# Sheet3.net
KiCad netlist of a schematic drawn in Altium Designer
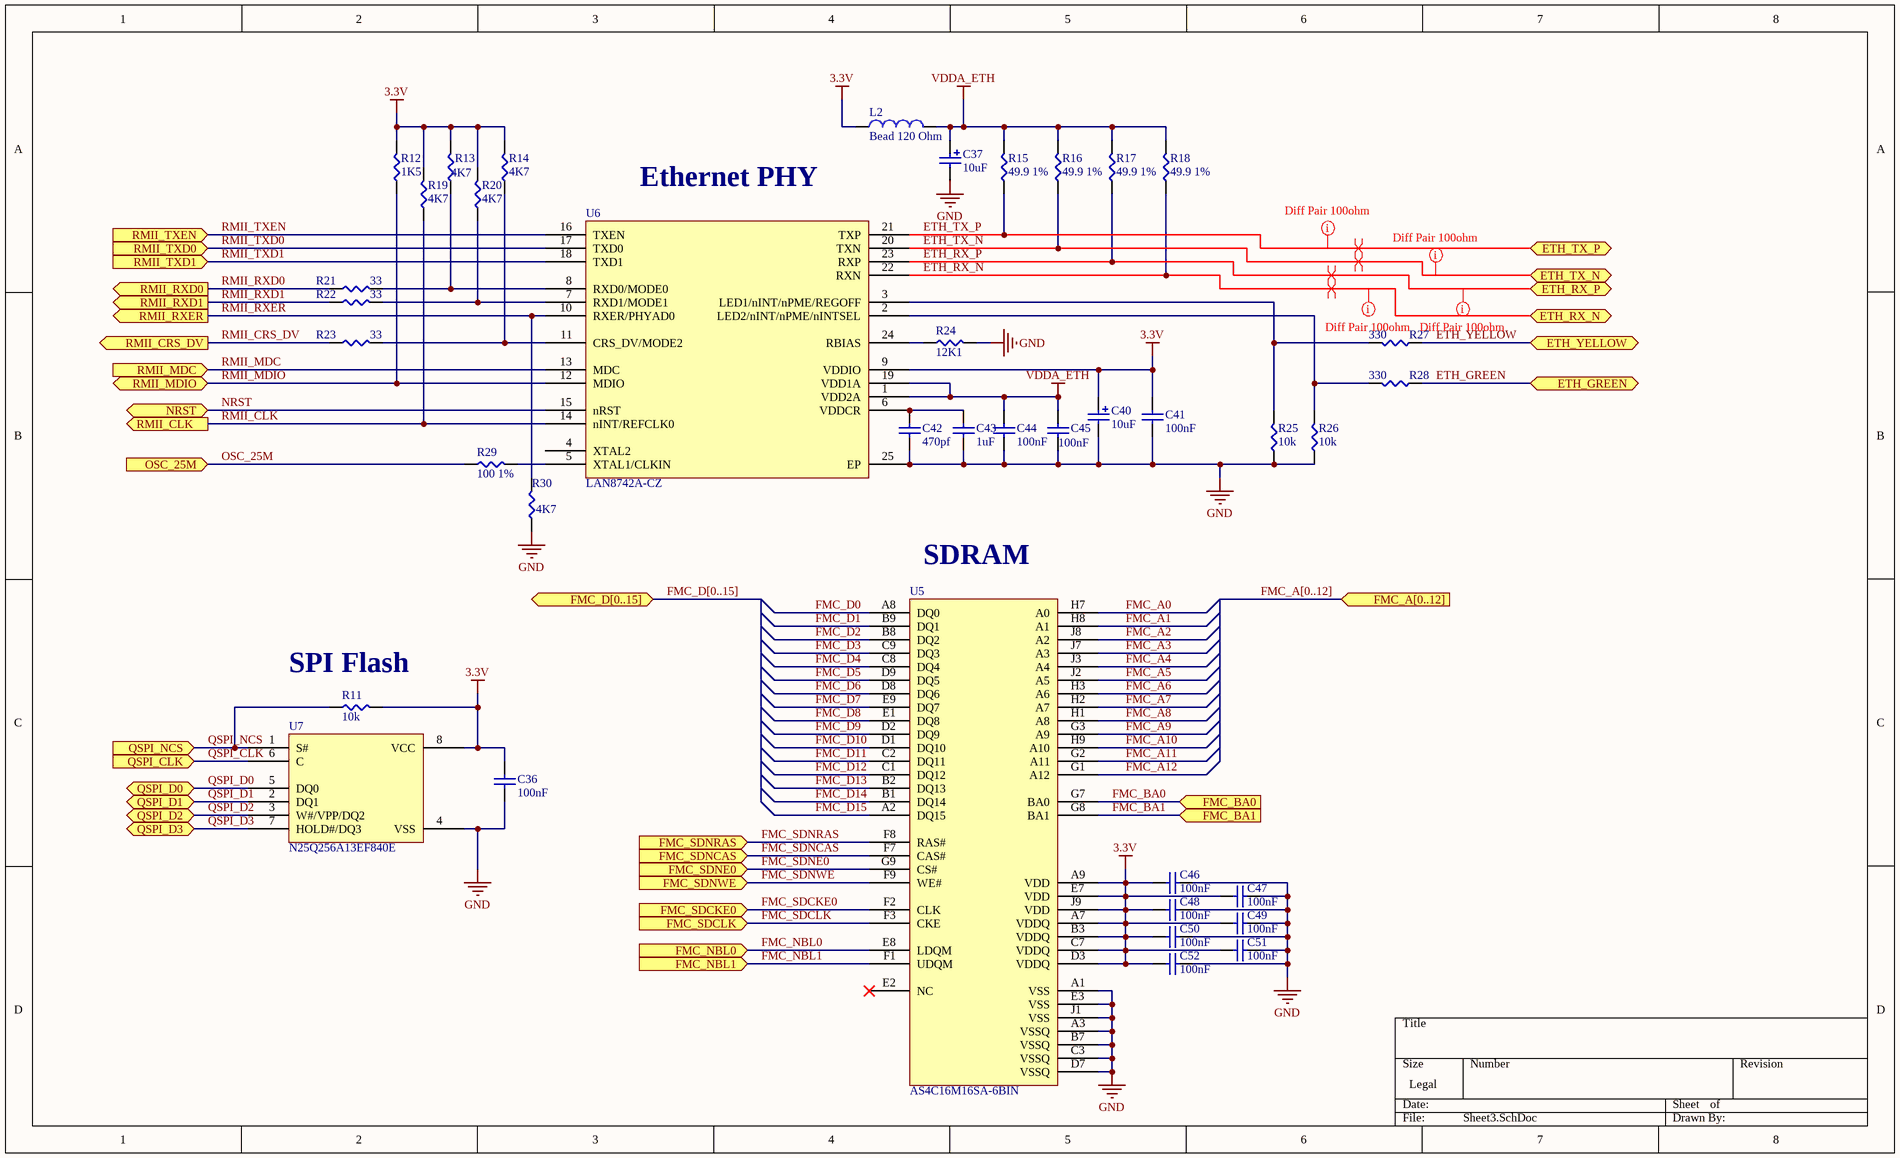
[diagram p0: Sheet3.SchDoc]

(export (version "E")
  (design (tool "Eeschema 10.0.6"))
  (components
    (comp (ref "C36")
      (value "100nF")
      (footprint "CAP0402X04M")
      (description "CAP CER 0.1UF 16V X7R 0402")
      (fields
        (field (name "MANUFACTURER") "Murata Electronics North America")
        (field (name "MANUFACTURER PART NUMBER") "GRM155R71C104KA88J")
      )
      (libsource (lib "Main") (part "GRM155R71C104KA88J"))
    )
    (comp (ref "C37")
      (value "10uF")
      (footprint "CAPPOL1206X07M")
      (description "CAP TANT 10UF 10V 10% 1206")
      (fields
        (field (name "MANUFACTURER") "Vishay Sprague")
        (field (name "MANUFACTURER PART NUMBER") "293D106X9010A2TE3")
      )
      (libsource (lib "Main") (part "293D106X9010A2TE3"))
    )
    (comp (ref "C40")
      (value "10uF")
      (footprint "CAPPOL1206X07M")
      (description "CAP TANT 10UF 10V 10% 1206")
      (fields
        (field (name "MANUFACTURER") "Vishay Sprague")
        (field (name "MANUFACTURER PART NUMBER") "293D106X9010A2TE3")
      )
      (libsource (lib "Main") (part "293D106X9010A2TE3"))
    )
    (comp (ref "C41")
      (value "100nF")
      (footprint "CAP0402X04M")
      (description "CAP CER 0.1UF 16V X7R 0402")
      (fields
        (field (name "MANUFACTURER") "Murata Electronics North America")
        (field (name "MANUFACTURER PART NUMBER") "GRM155R71C104KA88J")
      )
      (libsource (lib "Main") (part "GRM155R71C104KA88J"))
    )
    (comp (ref "C42")
      (value "470pf")
      (footprint "CAP0402X04M")
      (description "CAP CER 470PF 50V X7R 0402")
      (fields
        (field (name "MANUFACTURER") "Samsung Electro-Mechanics America, Inc.")
        (field (name "MANUFACTURER PART NUMBER") "CL05B471KB5NNNC")
      )
      (libsource (lib "Main") (part "CL05B471KB5NNNC"))
    )
    (comp (ref "C43")
      (value "1uF")
      (footprint "CAP0402X04M")
      (description "CAP CER 1UF 6.3V X5R 0402")
      (fields
        (field (name "MANUFACTURER") "Murata Electronics North America")
        (field (name "MANUFACTURER PART NUMBER") "GRM155R60J105KE19D")
      )
      (libsource (lib "Main") (part "GRM155R60J105KE19D"))
    )
    (comp (ref "C44")
      (value "100nF")
      (footprint "CAP0402X04M")
      (description "CAP CER 0.1UF 16V X7R 0402")
      (fields
        (field (name "MANUFACTURER") "Murata Electronics North America")
        (field (name "MANUFACTURER PART NUMBER") "GRM155R71C104KA88J")
      )
      (libsource (lib "Main") (part "GRM155R71C104KA88J"))
    )
    (comp (ref "C45")
      (value "100nF")
      (footprint "CAP0402X04M")
      (description "CAP CER 0.1UF 16V X7R 0402")
      (fields
        (field (name "MANUFACTURER") "Murata Electronics North America")
        (field (name "MANUFACTURER PART NUMBER") "GRM155R71C104KA88J")
      )
      (libsource (lib "Main") (part "GRM155R71C104KA88J"))
    )
    (comp (ref "C46")
      (value "100nF")
      (footprint "CAP0402X04M")
      (description "CAP CER 0.1UF 16V X7R 0402")
      (fields
        (field (name "MANUFACTURER") "Murata Electronics North America")
        (field (name "MANUFACTURER PART NUMBER") "GRM155R71C104KA88J")
      )
      (libsource (lib "Main") (part "GRM155R71C104KA88J"))
    )
    (comp (ref "C47")
      (value "100nF")
      (footprint "CAP0402X04M")
      (description "CAP CER 0.1UF 16V X7R 0402")
      (fields
        (field (name "MANUFACTURER") "Murata Electronics North America")
        (field (name "MANUFACTURER PART NUMBER") "GRM155R71C104KA88J")
      )
      (libsource (lib "Main") (part "GRM155R71C104KA88J"))
    )
    (comp (ref "C48")
      (value "100nF")
      (footprint "CAP0402X04ROUND")
      (description "CAP CER 0.1UF 16V X7R 0402")
      (fields
        (field (name "MANUFACTURER") "Murata Electronics North America")
        (field (name "MANUFACTURER PART NUMBER") "GRM155R71C104KA88J")
      )
      (libsource (lib "Main") (part "GRM155R71C104KA88J"))
    )
    (comp (ref "C49")
      (value "100nF")
      (footprint "CAP0402X04ROUND")
      (description "CAP CER 0.1UF 16V X7R 0402")
      (fields
        (field (name "MANUFACTURER") "Murata Electronics North America")
        (field (name "MANUFACTURER PART NUMBER") "GRM155R71C104KA88J")
      )
      (libsource (lib "Main") (part "GRM155R71C104KA88J"))
    )
    (comp (ref "C50")
      (value "100nF")
      (footprint "CAP0402X04ROUND")
      (description "CAP CER 0.1UF 16V X7R 0402")
      (fields
        (field (name "MANUFACTURER") "Murata Electronics North America")
        (field (name "MANUFACTURER PART NUMBER") "GRM155R71C104KA88J")
      )
      (libsource (lib "Main") (part "GRM155R71C104KA88J"))
    )
    (comp (ref "C51")
      (value "100nF")
      (footprint "CAP0402X04ROUND")
      (description "CAP CER 0.1UF 16V X7R 0402")
      (fields
        (field (name "MANUFACTURER") "Murata Electronics North America")
        (field (name "MANUFACTURER PART NUMBER") "GRM155R71C104KA88J")
      )
      (libsource (lib "Main") (part "GRM155R71C104KA88J"))
    )
    (comp (ref "C52")
      (value "100nF")
      (footprint "CAP0402X04ROUND")
      (description "CAP CER 0.1UF 16V X7R 0402")
      (fields
        (field (name "MANUFACTURER") "Murata Electronics North America")
        (field (name "MANUFACTURER PART NUMBER") "GRM155R71C104KA88J")
      )
      (libsource (lib "Main") (part "GRM155R71C104KA88J"))
    )
    (comp (ref "L2")
      (value "Bead 120 Ohm")
      (footprint "IND0603X055M")
      (description "FERRITE BEAD 120 OHM 0603 1LN")
      (fields
        (field (name "MANUFACTURER") "Murata Electronics North America")
        (field (name "MANUFACTURER PART NUMBER") "BLM18PG121SN1D")
      )
      (libsource (lib "Main") (part "BLM18PG121SN1D"))
    )
    (comp (ref "R11")
      (value "10k")
      (footprint "RES0402X04M")
      (description "RES SMD 10K OHM 1% 1/16W 0402")
      (fields
        (field (name "MANUFACTURER") "Yageo")
        (field (name "MANUFACTURER PART NUMBER") "RC0402FR-0710KL")
      )
      (libsource (lib "Main") (part "RC0402FR-0710KL"))
    )
    (comp (ref "R12")
      (value "1K5")
      (footprint "RES0402X04M")
      (description "RES SMD 1.5K OHM 1% 1/10W 0402")
      (fields
        (field (name "MANUFACTURER") "Panasonic Electronic Components")
        (field (name "MANUFACTURER PART NUMBER") "ERJ-2RKF1501X")
      )
      (libsource (lib "Main") (part "ERJ-2RKF1501X"))
    )
    (comp (ref "R13")
      (value "4K7")
      (footprint "RES0402X04M")
      (description "RES SMD 4.7K OHM 1% 1/10W 0402")
      (fields
        (field (name "MANUFACTURER") "Panasonic Electronic Components")
        (field (name "MANUFACTURER PART NUMBER") "ERJ-2RKF4701X")
      )
      (libsource (lib "Main") (part "ERJ-2RKF4701X"))
    )
    (comp (ref "R14")
      (value "4K7")
      (footprint "RES0402X04M")
      (description "RES SMD 4.7K OHM 1% 1/10W 0402")
      (fields
        (field (name "MANUFACTURER") "Panasonic Electronic Components")
        (field (name "MANUFACTURER PART NUMBER") "ERJ-2RKF4701X")
      )
      (libsource (lib "Main") (part "ERJ-2RKF4701X"))
    )
    (comp (ref "R15")
      (value "49.9 1%")
      (footprint "RES0402X04M")
      (description "RES SMD 49.9 OHM 1% 1/16W 0402")
      (fields
        (field (name "MANUFACTURER") "Yageo")
        (field (name "MANUFACTURER PART NUMBER") "RC0402FR-0749R9L")
      )
      (libsource (lib "Main") (part "RC0402FR-0749R9L"))
    )
    (comp (ref "R16")
      (value "49.9 1%")
      (footprint "RES0402X04M")
      (description "RES SMD 49.9 OHM 1% 1/16W 0402")
      (fields
        (field (name "MANUFACTURER") "Yageo")
        (field (name "MANUFACTURER PART NUMBER") "RC0402FR-0749R9L")
      )
      (libsource (lib "Main") (part "RC0402FR-0749R9L"))
    )
    (comp (ref "R17")
      (value "49.9 1%")
      (footprint "RES0402X04M")
      (description "RES SMD 49.9 OHM 1% 1/16W 0402")
      (fields
        (field (name "MANUFACTURER") "Yageo")
        (field (name "MANUFACTURER PART NUMBER") "RC0402FR-0749R9L")
      )
      (libsource (lib "Main") (part "RC0402FR-0749R9L"))
    )
    (comp (ref "R18")
      (value "49.9 1%")
      (footprint "RES0402X04M")
      (description "RES SMD 49.9 OHM 1% 1/16W 0402")
      (fields
        (field (name "MANUFACTURER") "Yageo")
        (field (name "MANUFACTURER PART NUMBER") "RC0402FR-0749R9L")
      )
      (libsource (lib "Main") (part "RC0402FR-0749R9L"))
    )
    (comp (ref "R19")
      (value "4K7")
      (footprint "RES0402X04M")
      (description "RES SMD 4.7K OHM 1% 1/10W 0402")
      (fields
        (field (name "MANUFACTURER") "Panasonic Electronic Components")
        (field (name "MANUFACTURER PART NUMBER") "ERJ-2RKF4701X")
      )
      (libsource (lib "Main") (part "ERJ-2RKF4701X"))
    )
    (comp (ref "R20")
      (value "4K7")
      (footprint "RES0402X04M")
      (description "RES SMD 4.7K OHM 1% 1/10W 0402")
      (fields
        (field (name "MANUFACTURER") "Panasonic Electronic Components")
        (field (name "MANUFACTURER PART NUMBER") "ERJ-2RKF4701X")
      )
      (libsource (lib "Main") (part "ERJ-2RKF4701X"))
    )
    (comp (ref "R21")
      (value "33")
      (footprint "RES0402X04M")
      (description "RES SMD 33 OHM 1% 1/10W 0402")
      (fields
        (field (name "MANUFACTURER") "Panasonic Electronic Components")
        (field (name "MANUFACTURER PART NUMBER") "ERJ-2RKF33R0X")
      )
      (libsource (lib "Main") (part "ERJ-2RKF33R0X"))
    )
    (comp (ref "R22")
      (value "33")
      (footprint "RES0402X04M")
      (description "RES SMD 33 OHM 1% 1/10W 0402")
      (fields
        (field (name "MANUFACTURER") "Panasonic Electronic Components")
        (field (name "MANUFACTURER PART NUMBER") "ERJ-2RKF33R0X")
      )
      (libsource (lib "Main") (part "ERJ-2RKF33R0X"))
    )
    (comp (ref "R23")
      (value "33")
      (footprint "RES0402X04M")
      (description "RES SMD 33 OHM 1% 1/10W 0402")
      (fields
        (field (name "MANUFACTURER") "Panasonic Electronic Components")
        (field (name "MANUFACTURER PART NUMBER") "ERJ-2RKF33R0X")
      )
      (libsource (lib "Main") (part "ERJ-2RKF33R0X"))
    )
    (comp (ref "R24")
      (value "12K1")
      (footprint "RES0402X04M")
      (description "RES SMD 12.1K OHM 1% 1/10W 0402")
      (fields
        (field (name "MANUFACTURER") "Panasonic Electronic Components")
        (field (name "MANUFACTURER PART NUMBER") "ERJ-2RKF1212X")
      )
      (libsource (lib "Main") (part "ERJ-2RKF1212X"))
    )
    (comp (ref "R25")
      (value "10k")
      (footprint "RES0402X04M")
      (description "RES SMD 10K OHM 1% 1/16W 0402")
      (fields
        (field (name "MANUFACTURER") "Yageo")
        (field (name "MANUFACTURER PART NUMBER") "RC0402FR-0710KL")
      )
      (libsource (lib "Main") (part "RC0402FR-0710KL"))
    )
    (comp (ref "R26")
      (value "10k")
      (footprint "RES0402X04M")
      (description "RES SMD 10K OHM 1% 1/16W 0402")
      (fields
        (field (name "MANUFACTURER") "Yageo")
        (field (name "MANUFACTURER PART NUMBER") "RC0402FR-0710KL")
      )
      (libsource (lib "Main") (part "RC0402FR-0710KL"))
    )
    (comp (ref "R27")
      (value "330")
      (footprint "RES0402X04M")
      (description "RES SMD 330 OHM 1% 1/10W 0402")
      (fields
        (field (name "MANUFACTURER") "Panasonic Electronic Components")
        (field (name "MANUFACTURER PART NUMBER") "ERJ-2RKF3300X")
      )
      (libsource (lib "Main") (part "ERJ-2RKF3300X"))
    )
    (comp (ref "R28")
      (value "330")
      (footprint "RES0402X04M")
      (description "RES SMD 330 OHM 1% 1/10W 0402")
      (fields
        (field (name "MANUFACTURER") "Panasonic Electronic Components")
        (field (name "MANUFACTURER PART NUMBER") "ERJ-2RKF3300X")
      )
      (libsource (lib "Main") (part "ERJ-2RKF3300X"))
    )
    (comp (ref "R29")
      (value "100 1%")
      (footprint "RES0402X04M")
      (description "RES SMD 100 OHM 1% 1/16W 0402")
      (fields
        (field (name "MANUFACTURER") "Yageo")
        (field (name "MANUFACTURER PART NUMBER") "RC0402FR-07100RL")
      )
      (libsource (lib "Main") (part "RC0402FR-07100RL"))
    )
    (comp (ref "R30")
      (value "4K7")
      (footprint "RES0402X04M")
      (description "RES SMD 4.7K OHM 1% 1/10W 0402")
      (fields
        (field (name "MANUFACTURER") "Panasonic Electronic Components")
        (field (name "MANUFACTURER PART NUMBER") "ERJ-2RKF4701X")
      )
      (libsource (lib "Main") (part "ERJ-2RKF4701X"))
    )
    (comp (ref "U5")
      (value "AS4C16M16SA-6BIN")
      (footprint "BGA100P9X9-54A")
      (description "IC SDRAM 256MBIT 166MHZ 54BGA")
      (fields (field (name "MANUFACTURER") "Alliance Memory, Inc."))
      (libsource (lib "Main") (part "AS4C16M16SA-6BIN"))
    )
    (comp (ref "U6")
      (value "LAN8742A-CZ")
      (footprint "QFN50P400X400X100_HS-25N")
      (description "IC TXRX ETHERNET 100MBPS 24QFN")
      (fields (field (name "MANUFACTURER") "Microchip Technology"))
      (libsource (lib "Main") (part "LAN8742A-CZ"))
    )
    (comp (ref "U7")
      (value "N25Q256A13EF840E")
      (footprint "SON127P800X100_HS-9N")
      (description "IC FLASH 256MBIT 108MHZ 8VPDFN")
      (fields (field (name "MANUFACTURER") "Micron Technology Inc."))
      (libsource (lib "Main") (part "N25Q256A13EF840E"))
    )
  )
  (nets
    (net (code "1") (name "/ETH_GREEN") (class "Default")
      (node (ref "R28") (pin "1") (pinfunction "1_1") (pintype "passive"))
    )
    (net (code "2") (name "/ETH_RX_N") (class "Default")
      (node (ref "R18") (pin "1") (pinfunction "1_1") (pintype "passive"))
      (node (ref "U6") (pin "22") (pinfunction "RXN_22") (pintype "passive"))
    )
    (net (code "3") (name "/ETH_RX_P") (class "Default")
      (node (ref "R17") (pin "1") (pinfunction "1_1") (pintype "passive"))
      (node (ref "U6") (pin "23") (pinfunction "RXP_23") (pintype "passive"))
    )
    (net (code "4") (name "/ETH_TX_N") (class "Default")
      (node (ref "R16") (pin "1") (pinfunction "1_1") (pintype "passive"))
      (node (ref "U6") (pin "20") (pinfunction "TXN_20") (pintype "passive"))
    )
    (net (code "5") (name "/ETH_TX_P") (class "Default")
      (node (ref "R15") (pin "1") (pinfunction "1_1") (pintype "passive"))
      (node (ref "U6") (pin "21") (pinfunction "TXP_21") (pintype "passive"))
    )
    (net (code "6") (name "/ETH_YELLOW") (class "Default")
      (node (ref "R27") (pin "1") (pinfunction "1_1") (pintype "passive"))
    )
    (net (code "7") (name "/FMC_A0") (class "Default")
      (node (ref "U5") (pin "H7") (pinfunction "A0_H7") (pintype "passive"))
    )
    (net (code "8") (name "/FMC_A1") (class "Default")
      (node (ref "U5") (pin "H8") (pinfunction "A1_H8") (pintype "passive"))
    )
    (net (code "9") (name "/FMC_A2") (class "Default")
      (node (ref "U5") (pin "J8") (pinfunction "A2_J8") (pintype "passive"))
    )
    (net (code "10") (name "/FMC_A3") (class "Default")
      (node (ref "U5") (pin "J7") (pinfunction "A3_J7") (pintype "passive"))
    )
    (net (code "11") (name "/FMC_A4") (class "Default")
      (node (ref "U5") (pin "J3") (pinfunction "A4_J3") (pintype "passive"))
    )
    (net (code "12") (name "/FMC_A5") (class "Default")
      (node (ref "U5") (pin "J2") (pinfunction "A5_J2") (pintype "passive"))
    )
    (net (code "13") (name "/FMC_A6") (class "Default")
      (node (ref "U5") (pin "H3") (pinfunction "A6_H3") (pintype "passive"))
    )
    (net (code "14") (name "/FMC_A7") (class "Default")
      (node (ref "U5") (pin "H2") (pinfunction "A7_H2") (pintype "passive"))
    )
    (net (code "15") (name "/FMC_A8") (class "Default")
      (node (ref "U5") (pin "H1") (pinfunction "A8_H1") (pintype "passive"))
    )
    (net (code "16") (name "/FMC_A9") (class "Default")
      (node (ref "U5") (pin "G3") (pinfunction "A9_G3") (pintype "passive"))
    )
    (net (code "17") (name "/FMC_A10") (class "Default")
      (node (ref "U5") (pin "H9") (pinfunction "A10_H9") (pintype "passive"))
    )
    (net (code "18") (name "/FMC_A11") (class "Default")
      (node (ref "U5") (pin "G2") (pinfunction "A11_G2") (pintype "passive"))
    )
    (net (code "19") (name "/FMC_A12") (class "Default")
      (node (ref "U5") (pin "G1") (pinfunction "A12_G1") (pintype "passive"))
    )
    (net (code "21") (name "/FMC_BA0") (class "Default")
      (node (ref "U5") (pin "G7") (pinfunction "BA0_G7") (pintype "passive"))
    )
    (net (code "22") (name "/FMC_BA1") (class "Default")
      (node (ref "U5") (pin "G8") (pinfunction "BA1_G8") (pintype "passive"))
    )
    (net (code "23") (name "/FMC_D0") (class "Default")
      (node (ref "U5") (pin "A8") (pinfunction "DQ0_A8") (pintype "passive"))
    )
    (net (code "24") (name "/FMC_D1") (class "Default")
      (node (ref "U5") (pin "B9") (pinfunction "DQ1_B9") (pintype "passive"))
    )
    (net (code "25") (name "/FMC_D2") (class "Default")
      (node (ref "U5") (pin "B8") (pinfunction "DQ2_B8") (pintype "passive"))
    )
    (net (code "26") (name "/FMC_D3") (class "Default")
      (node (ref "U5") (pin "C9") (pinfunction "DQ3_C9") (pintype "passive"))
    )
    (net (code "27") (name "/FMC_D4") (class "Default")
      (node (ref "U5") (pin "C8") (pinfunction "DQ4_C8") (pintype "passive"))
    )
    (net (code "28") (name "/FMC_D5") (class "Default")
      (node (ref "U5") (pin "D9") (pinfunction "DQ5_D9") (pintype "passive"))
    )
    (net (code "29") (name "/FMC_D6") (class "Default")
      (node (ref "U5") (pin "D8") (pinfunction "DQ6_D8") (pintype "passive"))
    )
    (net (code "30") (name "/FMC_D7") (class "Default")
      (node (ref "U5") (pin "E9") (pinfunction "DQ7_E9") (pintype "passive"))
    )
    (net (code "31") (name "/FMC_D8") (class "Default")
      (node (ref "U5") (pin "E1") (pinfunction "DQ8_E1") (pintype "passive"))
    )
    (net (code "32") (name "/FMC_D9") (class "Default")
      (node (ref "U5") (pin "D2") (pinfunction "DQ9_D2") (pintype "passive"))
    )
    (net (code "33") (name "/FMC_D10") (class "Default")
      (node (ref "U5") (pin "D1") (pinfunction "DQ10_D1") (pintype "passive"))
    )
    (net (code "34") (name "/FMC_D11") (class "Default")
      (node (ref "U5") (pin "C2") (pinfunction "DQ11_C2") (pintype "passive"))
    )
    (net (code "35") (name "/FMC_D12") (class "Default")
      (node (ref "U5") (pin "C1") (pinfunction "DQ12_C1") (pintype "passive"))
    )
    (net (code "36") (name "/FMC_D13") (class "Default")
      (node (ref "U5") (pin "B2") (pinfunction "DQ13_B2") (pintype "passive"))
    )
    (net (code "37") (name "/FMC_D14") (class "Default")
      (node (ref "U5") (pin "B1") (pinfunction "DQ14_B1") (pintype "passive"))
    )
    (net (code "38") (name "/FMC_D15") (class "Default")
      (node (ref "U5") (pin "A2") (pinfunction "DQ15_A2") (pintype "passive"))
    )
    (net (code "40") (name "/FMC_NBL0") (class "Default")
      (node (ref "U5") (pin "E8") (pinfunction "LDQM_E8") (pintype "passive"))
    )
    (net (code "41") (name "/FMC_NBL1") (class "Default")
      (node (ref "U5") (pin "F1") (pinfunction "UDQM_F1") (pintype "passive"))
    )
    (net (code "42") (name "/FMC_SDCKE0") (class "Default")
      (node (ref "U5") (pin "F2") (pinfunction "CLK_F2") (pintype "passive"))
    )
    (net (code "43") (name "/FMC_SDCLK") (class "Default")
      (node (ref "U5") (pin "F3") (pinfunction "CKE_F3") (pintype "passive"))
    )
    (net (code "44") (name "/FMC_SDNCAS") (class "Default")
      (node (ref "U5") (pin "F7") (pinfunction "CAS#_F7") (pintype "passive"))
    )
    (net (code "45") (name "/FMC_SDNE0") (class "Default")
      (node (ref "U5") (pin "G9") (pinfunction "CS#_G9") (pintype "passive"))
    )
    (net (code "46") (name "/FMC_SDNRAS") (class "Default")
      (node (ref "U5") (pin "F8") (pinfunction "RAS#_F8") (pintype "passive"))
    )
    (net (code "47") (name "/FMC_SDNWE") (class "Default")
      (node (ref "U5") (pin "F9") (pinfunction "WE#_F9") (pintype "passive"))
    )
    (net (code "48") (name "/NRST") (class "Default")
      (node (ref "U6") (pin "15") (pinfunction "nRST_15") (pintype "passive"))
    )
    (net (code "49") (name "/OSC_25M") (class "Default")
      (node (ref "R29") (pin "1") (pinfunction "1_1") (pintype "passive"))
    )
    (net (code "50") (name "/QSPI_CLK") (class "Default")
      (node (ref "U7") (pin "6") (pinfunction "C_6") (pintype "passive"))
    )
    (net (code "51") (name "/QSPI_D0") (class "Default")
      (node (ref "U7") (pin "5") (pinfunction "DQ0_5") (pintype "passive"))
    )
    (net (code "52") (name "/QSPI_D1") (class "Default")
      (node (ref "U7") (pin "2") (pinfunction "DQ1_2") (pintype "passive"))
    )
    (net (code "53") (name "/QSPI_D2") (class "Default")
      (node (ref "U7") (pin "3") (pinfunction "W#/VPP/DQ2_3") (pintype "passive"))
    )
    (net (code "54") (name "/QSPI_D3") (class "Default")
      (node (ref "U7") (pin "7") (pinfunction "HOLD#/DQ3_7") (pintype "passive"))
    )
    (net (code "55") (name "/QSPI_NCS") (class "Default")
      (node (ref "R11") (pin "1") (pinfunction "1_1") (pintype "passive"))
      (node (ref "U7") (pin "1") (pinfunction "S#_1") (pintype "passive"))
    )
    (net (code "56") (name "/RMII_CLK") (class "Default")
      (node (ref "R19") (pin "1") (pinfunction "1_1") (pintype "passive"))
      (node (ref "U6") (pin "14") (pinfunction "nINT/REFCLK0_14") (pintype "passive"))
    )
    (net (code "57") (name "/RMII_CRS_DV") (class "Default")
      (node (ref "R23") (pin "1") (pinfunction "1_1") (pintype "passive"))
    )
    (net (code "58") (name "/RMII_MDC") (class "Default")
      (node (ref "U6") (pin "13") (pinfunction "MDC_13") (pintype "passive"))
    )
    (net (code "59") (name "/RMII_MDIO") (class "Default")
      (node (ref "R12") (pin "1") (pinfunction "1_1") (pintype "passive"))
      (node (ref "U6") (pin "12") (pinfunction "MDIO_12") (pintype "passive"))
    )
    (net (code "60") (name "/RMII_RXD0") (class "Default")
      (node (ref "R21") (pin "1") (pinfunction "1_1") (pintype "passive"))
    )
    (net (code "61") (name "/RMII_RXD1") (class "Default")
      (node (ref "R22") (pin "1") (pinfunction "1_1") (pintype "passive"))
    )
    (net (code "62") (name "/RMII_RXER") (class "Default")
      (node (ref "R30") (pin "2") (pinfunction "2_2") (pintype "passive"))
      (node (ref "U6") (pin "10") (pinfunction "RXER/PHYAD0_10") (pintype "passive"))
    )
    (net (code "63") (name "/RMII_TXD0") (class "Default")
      (node (ref "U6") (pin "17") (pinfunction "TXD0_17") (pintype "passive"))
    )
    (net (code "64") (name "/RMII_TXD1") (class "Default")
      (node (ref "U6") (pin "18") (pinfunction "TXD1_18") (pintype "passive"))
    )
    (net (code "65") (name "/RMII_TXEN") (class "Default")
      (node (ref "U6") (pin "16") (pinfunction "TXEN_16") (pintype "passive"))
    )
    (net (code "66") (name "3.3V") (class "Default")
      (node (ref "C36") (pin "2") (pinfunction "2_2") (pintype "passive"))
      (node (ref "C40") (pin "1") (pinfunction "1_1") (pintype "passive"))
      (node (ref "C41") (pin "2") (pinfunction "2_2") (pintype "passive"))
      (node (ref "C46") (pin "1") (pinfunction "1_1") (pintype "passive"))
      (node (ref "C47") (pin "1") (pinfunction "1_1") (pintype "passive"))
      (node (ref "C48") (pin "1") (pinfunction "1_1") (pintype "passive"))
      (node (ref "C49") (pin "1") (pinfunction "1_1") (pintype "passive"))
      (node (ref "C50") (pin "1") (pinfunction "1_1") (pintype "passive"))
      (node (ref "C51") (pin "1") (pinfunction "1_1") (pintype "passive"))
      (node (ref "C52") (pin "1") (pinfunction "1_1") (pintype "passive"))
      (node (ref "L2") (pin "1") (pinfunction "1_1") (pintype "passive"))
      (node (ref "R11") (pin "2") (pinfunction "2_2") (pintype "passive"))
      (node (ref "R12") (pin "2") (pinfunction "2_2") (pintype "passive"))
      (node (ref "R13") (pin "2") (pinfunction "2_2") (pintype "passive"))
      (node (ref "R14") (pin "2") (pinfunction "2_2") (pintype "passive"))
      (node (ref "R19") (pin "2") (pinfunction "2_2") (pintype "passive"))
      (node (ref "R20") (pin "2") (pinfunction "2_2") (pintype "passive"))
      (node (ref "U5") (pin "A7") (pinfunction "VDDQ_A7") (pintype "passive"))
      (node (ref "U5") (pin "A9") (pinfunction "VDD_A9") (pintype "passive"))
      (node (ref "U5") (pin "B3") (pinfunction "VDDQ_B3") (pintype "passive"))
      (node (ref "U5") (pin "C7") (pinfunction "VDDQ_C7") (pintype "passive"))
      (node (ref "U5") (pin "D3") (pinfunction "VDDQ_D3") (pintype "passive"))
      (node (ref "U5") (pin "E7") (pinfunction "VDD_E7") (pintype "passive"))
      (node (ref "U5") (pin "J9") (pinfunction "VDD_J9") (pintype "passive"))
      (node (ref "U6") (pin "9") (pinfunction "VDDIO_9") (pintype "passive"))
      (node (ref "U7") (pin "8") (pinfunction "VCC_8") (pintype "passive"))
    )
    (net (code "67") (name "GND") (class "Default")
      (node (ref "C36") (pin "1") (pinfunction "1_1") (pintype "passive"))
      (node (ref "C37") (pin "2") (pinfunction "2_2") (pintype "passive"))
      (node (ref "C40") (pin "2") (pinfunction "2_2") (pintype "passive"))
      (node (ref "C41") (pin "1") (pinfunction "1_1") (pintype "passive"))
      (node (ref "C42") (pin "1") (pinfunction "1_1") (pintype "passive"))
      (node (ref "C43") (pin "1") (pinfunction "1_1") (pintype "passive"))
      (node (ref "C44") (pin "1") (pinfunction "1_1") (pintype "passive"))
      (node (ref "C45") (pin "1") (pinfunction "1_1") (pintype "passive"))
      (node (ref "C46") (pin "2") (pinfunction "2_2") (pintype "passive"))
      (node (ref "C47") (pin "2") (pinfunction "2_2") (pintype "passive"))
      (node (ref "C48") (pin "2") (pinfunction "2_2") (pintype "passive"))
      (node (ref "C49") (pin "2") (pinfunction "2_2") (pintype "passive"))
      (node (ref "C50") (pin "2") (pinfunction "2_2") (pintype "passive"))
      (node (ref "C51") (pin "2") (pinfunction "2_2") (pintype "passive"))
      (node (ref "C52") (pin "2") (pinfunction "2_2") (pintype "passive"))
      (node (ref "R24") (pin "2") (pinfunction "2_2") (pintype "passive"))
      (node (ref "R25") (pin "1") (pinfunction "1_1") (pintype "passive"))
      (node (ref "R26") (pin "1") (pinfunction "1_1") (pintype "passive"))
      (node (ref "R30") (pin "1") (pinfunction "1_1") (pintype "passive"))
      (node (ref "U5") (pin "A1") (pinfunction "VSS_A1") (pintype "passive"))
      (node (ref "U5") (pin "A3") (pinfunction "VSSQ_A3") (pintype "passive"))
      (node (ref "U5") (pin "B7") (pinfunction "VSSQ_B7") (pintype "passive"))
      (node (ref "U5") (pin "C3") (pinfunction "VSSQ_C3") (pintype "passive"))
      (node (ref "U5") (pin "D7") (pinfunction "VSSQ_D7") (pintype "passive"))
      (node (ref "U5") (pin "E3") (pinfunction "VSS_E3") (pintype "passive"))
      (node (ref "U5") (pin "J1") (pinfunction "VSS_J1") (pintype "passive"))
      (node (ref "U6") (pin "25") (pinfunction "EP_25") (pintype "passive"))
      (node (ref "U7") (pin "4") (pinfunction "VSS_4") (pintype "passive"))
    )
    (net (code "68") (name "Net-(U6-CRS_DV{slash}MODE2)") (class "Default")
      (node (ref "R14") (pin "1") (pinfunction "1_1") (pintype "passive"))
      (node (ref "R23") (pin "2") (pinfunction "2_2") (pintype "passive"))
      (node (ref "U6") (pin "11") (pinfunction "CRS_DV/MODE2_11") (pintype "passive"))
    )
    (net (code "69") (name "Net-(U6-LED1{slash}nINT{slash}nPME{slash}REGOFF)") (class "Default")
      (node (ref "R25") (pin "2") (pinfunction "2_2") (pintype "passive"))
      (node (ref "R27") (pin "2") (pinfunction "2_2") (pintype "passive"))
      (node (ref "U6") (pin "3") (pinfunction "LED1/nINT/nPME/REGOFF_3") (pintype "passive"))
    )
    (net (code "70") (name "Net-(U6-LED2{slash}nINT{slash}nPME{slash}nINTSEL)") (class "Default")
      (node (ref "R26") (pin "2") (pinfunction "2_2") (pintype "passive"))
      (node (ref "R28") (pin "2") (pinfunction "2_2") (pintype "passive"))
      (node (ref "U6") (pin "2") (pinfunction "LED2/nINT/nPME/nINTSEL_2") (pintype "passive"))
    )
    (net (code "71") (name "Net-(U6-RBIAS)") (class "Default")
      (node (ref "R24") (pin "1") (pinfunction "1_1") (pintype "passive"))
      (node (ref "U6") (pin "24") (pinfunction "RBIAS_24") (pintype "passive"))
    )
    (net (code "72") (name "Net-(U6-RXD0{slash}MODE0)") (class "Default")
      (node (ref "R13") (pin "1") (pinfunction "1_1") (pintype "passive"))
      (node (ref "R21") (pin "2") (pinfunction "2_2") (pintype "passive"))
      (node (ref "U6") (pin "8") (pinfunction "RXD0/MODE0_8") (pintype "passive"))
    )
    (net (code "73") (name "Net-(U6-RXD1{slash}MODE1)") (class "Default")
      (node (ref "R20") (pin "1") (pinfunction "1_1") (pintype "passive"))
      (node (ref "R22") (pin "2") (pinfunction "2_2") (pintype "passive"))
      (node (ref "U6") (pin "7") (pinfunction "RXD1/MODE1_7") (pintype "passive"))
    )
    (net (code "74") (name "Net-(U6-VDDCR)") (class "Default")
      (node (ref "C42") (pin "2") (pinfunction "2_2") (pintype "passive"))
      (node (ref "C43") (pin "2") (pinfunction "2_2") (pintype "passive"))
      (node (ref "U6") (pin "6") (pinfunction "VDDCR_6") (pintype "passive"))
    )
    (net (code "75") (name "Net-(U6-XTAL1{slash}CLKIN)") (class "Default")
      (node (ref "R29") (pin "2") (pinfunction "2_2") (pintype "passive"))
      (node (ref "U6") (pin "5") (pinfunction "XTAL1/CLKIN_5") (pintype "passive"))
    )
    (net (code "76") (name "VDDA_ETH") (class "Default")
      (node (ref "C37") (pin "1") (pinfunction "1_1") (pintype "passive"))
      (node (ref "C44") (pin "2") (pinfunction "2_2") (pintype "passive"))
      (node (ref "C45") (pin "2") (pinfunction "2_2") (pintype "passive"))
      (node (ref "L2") (pin "2") (pinfunction "2_2") (pintype "passive"))
      (node (ref "R15") (pin "2") (pinfunction "2_2") (pintype "passive"))
      (node (ref "R16") (pin "2") (pinfunction "2_2") (pintype "passive"))
      (node (ref "R17") (pin "2") (pinfunction "2_2") (pintype "passive"))
      (node (ref "R18") (pin "2") (pinfunction "2_2") (pintype "passive"))
      (node (ref "U6") (pin "1") (pinfunction "VDD2A_1") (pintype "passive"))
      (node (ref "U6") (pin "19") (pinfunction "VDD1A_19") (pintype "passive"))
    )
    (net (code "77") (name "unconnected-(U5-NC-PadE2)") (class "Default")
      (node (ref "U5") (pin "E2") (pinfunction "NC_E2") (pintype "passive+no_connect"))
    )
    (net (code "78") (name "unconnected-(U6-XTAL2-Pad4)") (class "Default")
      (node (ref "U6") (pin "4") (pinfunction "XTAL2_4") (pintype "passive"))
    )
  )
)
